# ProPrj_New_Project_2025-04-16_15-56-37_2.net
KiCad netlist of a schematic drawn in EasyEDA Pro
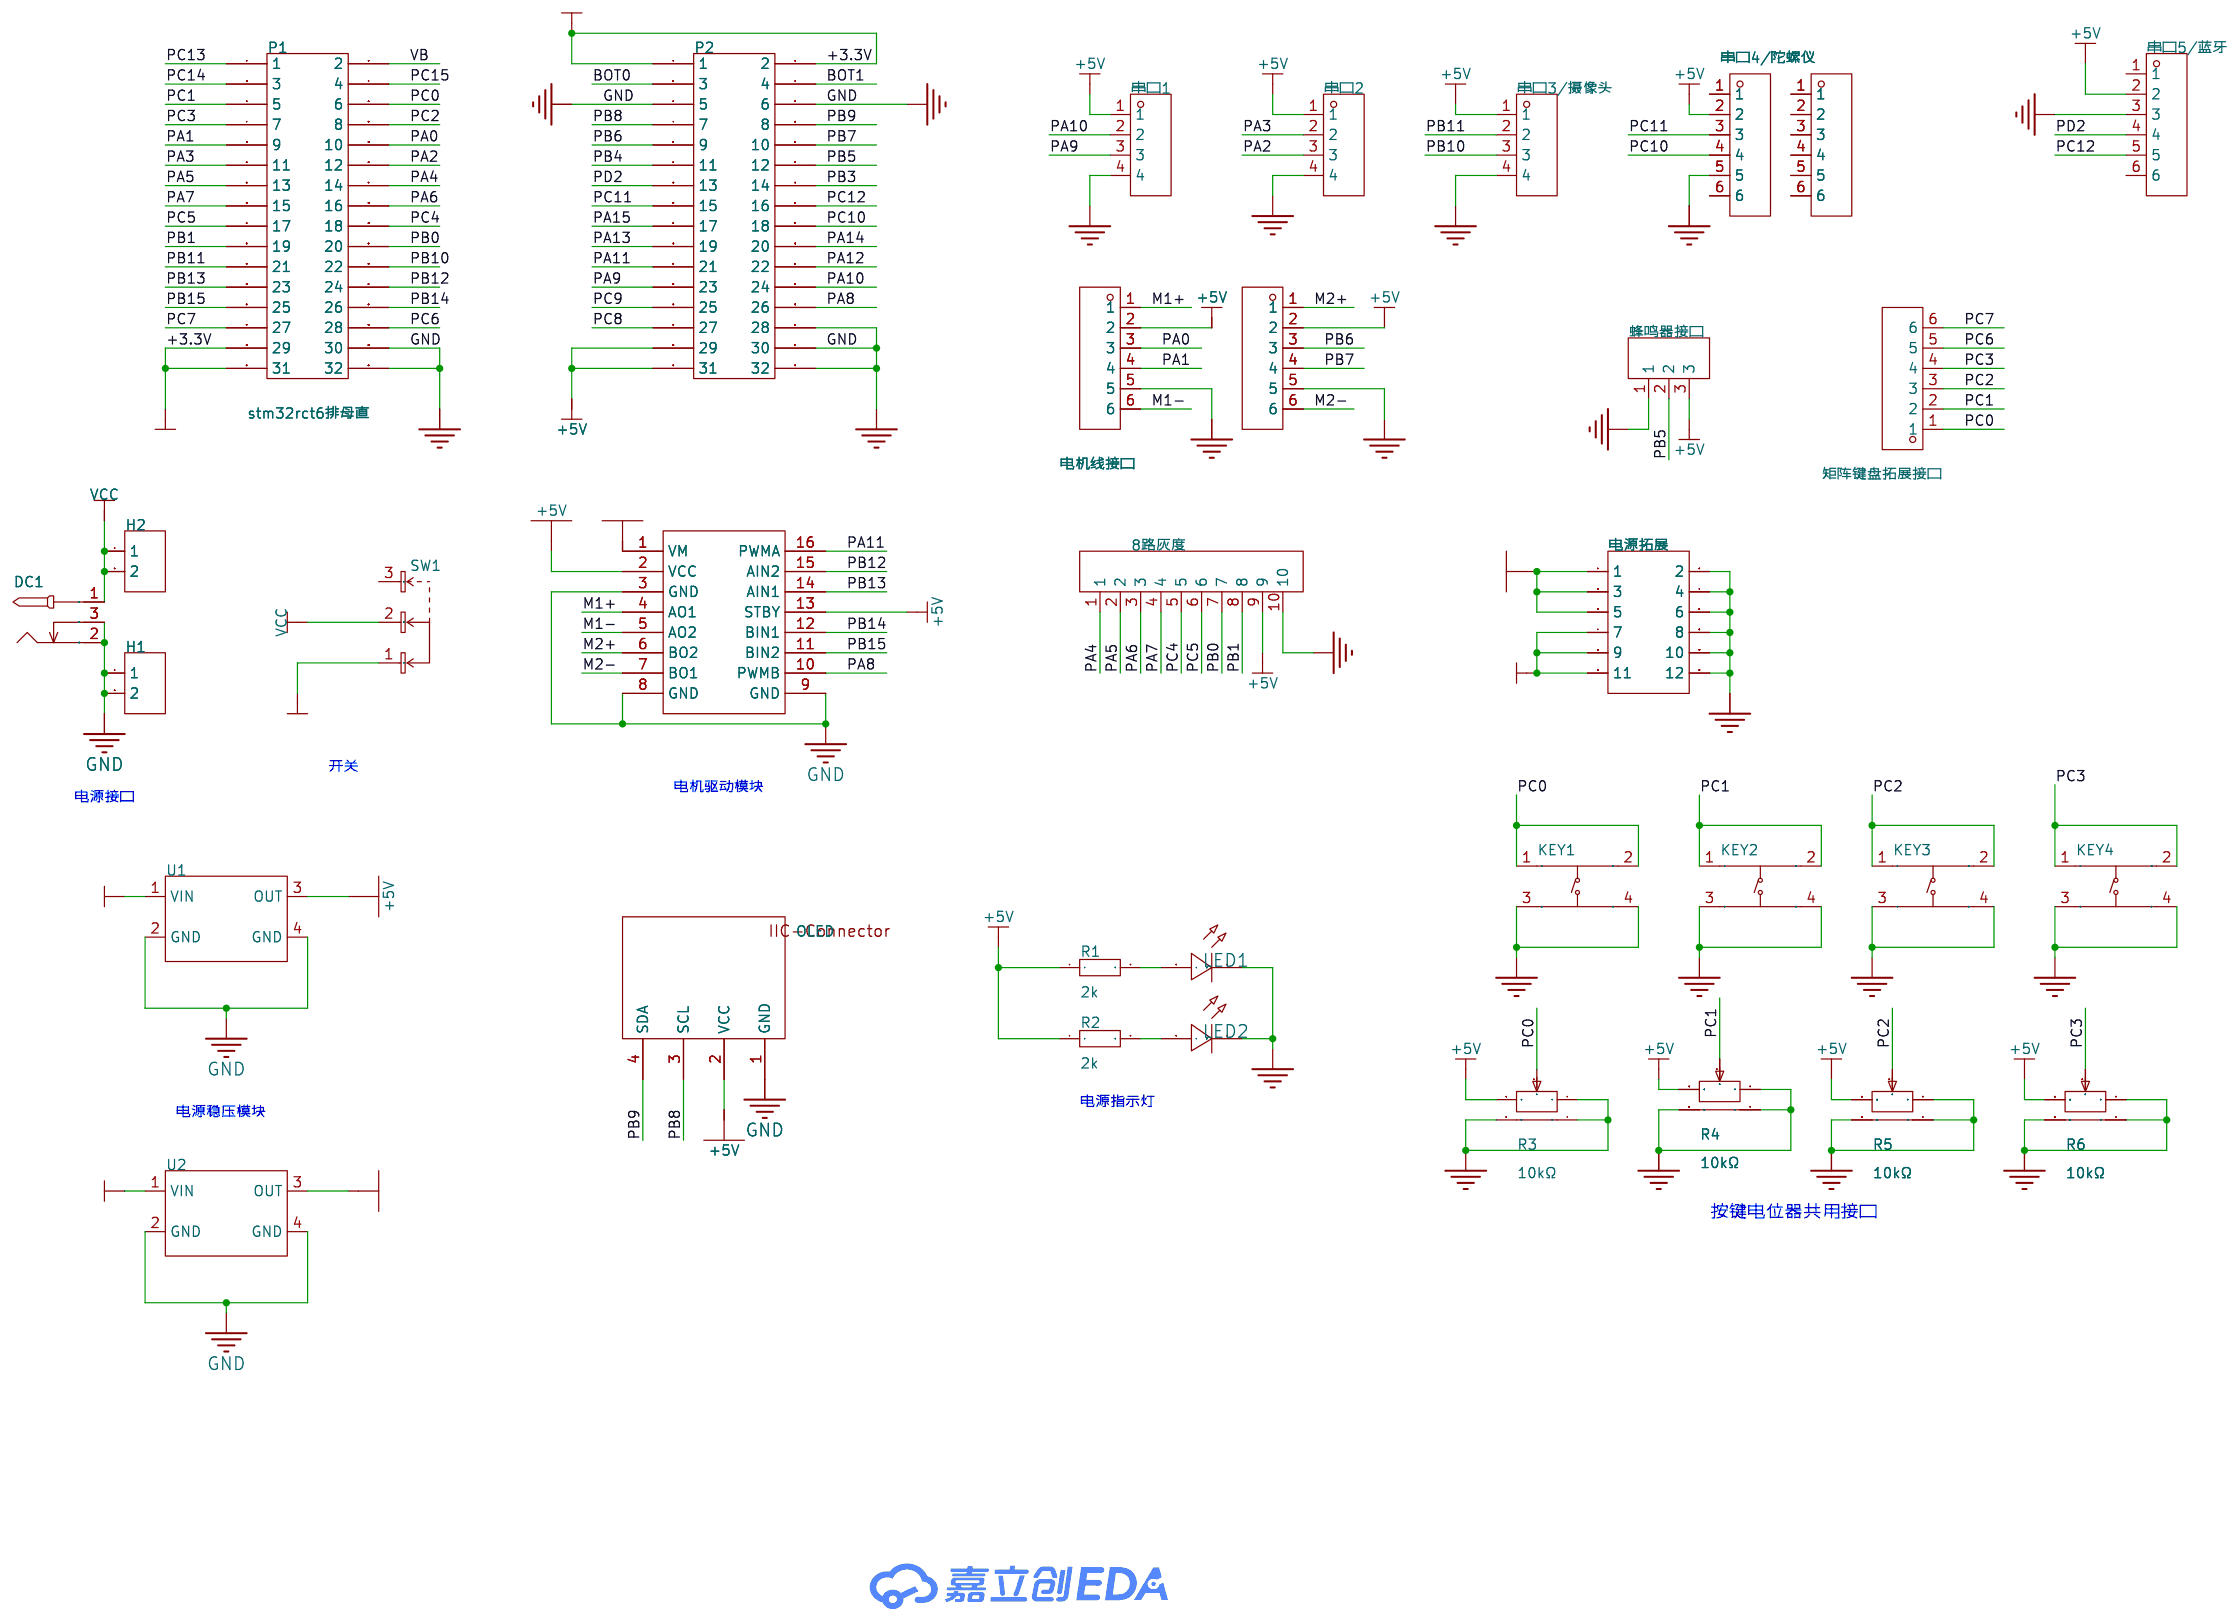
[diagram p0: schematic sheet]

(export (version "E")
  (design (tool "Eeschema 10.0.6"))
  (components
    (comp (ref "8路灰度")
      (value "~")
      (footprint "easyedapro:HDR-TH_10P-P2.54-V-F")
      (libsource (lib "easyedapro") (part "X5511FV-10-C70D30-1000"))
    )
    (comp (ref "DC1")
      (value "~")
      (footprint "easyedapro:DC-005_2.5")
      (libsource (lib "easyedapro") (part "DC-005_2.5"))
    )
    (comp (ref "H1")
      (value "~")
      (footprint "easyedapro:HDR-TH_2P-P2.54-V-F")
      (libsource (lib "easyedapro") (part "Header-Female-2.54_1x2"))
    )
    (comp (ref "H2")
      (value "~")
      (footprint "easyedapro:HDR-TH_2P-P2.54-V-F")
      (libsource (lib "easyedapro") (part "Header-Female-2.54_1x2"))
    )
    (comp (ref "H8")
      (value "~")
      (footprint "easyedapro:HDR-TH_6P-P2.54-V-F")
      (libsource (lib "easyedapro") (part "Header-Female-2.54_1x6"))
    )
    (comp (ref "KEY1")
      (value "TS665CJ")
      (footprint "easyedapro:SW-TH_4P-L6.0-W6.0-P4.50-LS6.5")
      (description "电路结构:单刀单掷;按钮形状:圆形按钮;安装方式:直插;开关长度:6mm;开关宽度:6mm;开关高度:5mm;触点电流:50mA;额定电压(DC):12V;带灯:-;机械寿命:-;")
      (fields (field (name "Manufacturer") "SHOU HAN(首韩)"))
      (libsource (lib "easyedapro") (part "TS665CJ"))
    )
    (comp (ref "KEY2")
      (value "TS665CJ")
      (footprint "easyedapro:SW-TH_4P-L6.0-W6.0-P4.50-LS6.5")
      (description "电路结构:单刀单掷;按钮形状:圆形按钮;安装方式:直插;开关长度:6mm;开关宽度:6mm;开关高度:5mm;触点电流:50mA;额定电压(DC):12V;带灯:-;机械寿命:-;")
      (fields (field (name "Manufacturer") "SHOU HAN(首韩)"))
      (libsource (lib "easyedapro") (part "TS665CJ"))
    )
    (comp (ref "KEY3")
      (value "TS665CJ")
      (footprint "easyedapro:SW-TH_4P-L6.0-W6.0-P4.50-LS6.5")
      (description "电路结构:单刀单掷;按钮形状:圆形按钮;安装方式:直插;开关长度:6mm;开关宽度:6mm;开关高度:5mm;触点电流:50mA;额定电压(DC):12V;带灯:-;机械寿命:-;")
      (fields (field (name "Manufacturer") "SHOU HAN(首韩)"))
      (libsource (lib "easyedapro") (part "TS665CJ"))
    )
    (comp (ref "KEY4")
      (value "TS665CJ")
      (footprint "easyedapro:SW-TH_4P-L6.0-W6.0-P4.50-LS6.5")
      (description "电路结构:单刀单掷;按钮形状:圆形按钮;安装方式:直插;开关长度:6mm;开关宽度:6mm;开关高度:5mm;触点电流:50mA;额定电压(DC):12V;带灯:-;机械寿命:-;")
      (fields (field (name "Manufacturer") "SHOU HAN(首韩)"))
      (libsource (lib "easyedapro") (part "TS665CJ"))
    )
    (comp (ref "LED1")
      (value "~")
      (footprint "easyedapro:LED_0603")
      (libsource (lib "easyedapro") (part "LED_R"))
    )
    (comp (ref "LED2")
      (value "~")
      (footprint "easyedapro:LED_0603")
      (libsource (lib "easyedapro") (part "LED_R"))
    )
    (comp (ref "OLED")
      (value "~")
      (fields (field (name "Manufacturer Part") "0.96OLED_4P_MODULE_JX"))
      (libsource (lib "easyedapro") (part "0.96OLED_4P_MODULE_JX"))
    )
    (comp (ref "P1")
      (value "stm32rct6排母直")
      (footprint "easyedapro:HDR-TH_32P-P2.54-V-F-R2-C16-S2.54")
      (description "圆针/方针:-;额定电流:-;额定电压:-;配合针长度:-;塑高:-;触头材质:-;")
      (libsource (lib "easyedapro") (part "2.54mm,2×16Double row female"))
    )
    (comp (ref "P2")
      (value "stm32rct6排母直")
      (footprint "easyedapro:HDR-TH_32P-P2.54-V-F-R2-C16-S2.54")
      (description "圆针/方针:-;额定电流:-;额定电压:-;配合针长度:-;塑高:-;触头材质:-;")
      (libsource (lib "easyedapro") (part "2.54mm,2×16Double row female"))
    )
    (comp (ref "R1") (value "2k") (footprint "easyedapro:R0603") (libsource (lib "easyedapro") (part "电阻")))
    (comp (ref "R2") (value "2k") (footprint "easyedapro:R0603") (libsource (lib "easyedapro") (part "电阻")))
    (comp (ref "R3")
      (value "10kΩ")
      (footprint "easyedapro:RES-ADJ-TH_RK09K1130AJ3")
      (description "阻值:10kΩ;精度:±20%;功率:50mW;")
      (fields
        (field (name "Manufacturer Part") "RK09K1130AP5")
        (field (name "Manufacturer") "ALPSALPINE(阿尔卑斯阿尔派)")
      )
      (libsource (lib "easyedapro") (part "RK09K1130AP5"))
    )
    (comp (ref "R4")
      (value "10kΩ")
      (footprint "easyedapro:RES-ADJ-TH_RK09K1130AJ3")
      (description "阻值:10kΩ;精度:±20%;功率:50mW;")
      (fields
        (field (name "Manufacturer Part") "RK09K1130AP5")
        (field (name "Manufacturer") "ALPSALPINE(阿尔卑斯阿尔派)")
      )
      (libsource (lib "easyedapro") (part "RK09K1130AP5"))
    )
    (comp (ref "R5")
      (value "10kΩ")
      (footprint "easyedapro:RES-ADJ-TH_RK09K1130AJ3")
      (description "阻值:10kΩ;精度:±20%;功率:50mW;")
      (fields
        (field (name "Manufacturer Part") "RK09K1130AP5")
        (field (name "Manufacturer") "ALPSALPINE(阿尔卑斯阿尔派)")
      )
      (libsource (lib "easyedapro") (part "RK09K1130AP5"))
    )
    (comp (ref "R6")
      (value "10kΩ")
      (footprint "easyedapro:RES-ADJ-TH_RK09K1130AJ3")
      (description "阻值:10kΩ;精度:±20%;功率:50mW;")
      (fields
        (field (name "Manufacturer Part") "RK09K1130AP5")
        (field (name "Manufacturer") "ALPSALPINE(阿尔卑斯阿尔派)")
      )
      (libsource (lib "easyedapro") (part "RK09K1130AP5"))
    )
    (comp (ref "SW1")
      (value "SS-12D06L5")
      (footprint "easyedapro:SW-TH_3P-P4.70_L11.1-W12.7")
      (description "电路结构:单刀双掷;安装方式:侧插;开关颜色:黑色;额定电流(DC):3A;额定电压(DC):250V;额定电流(AC):3A;额定电压(AC):250V;机械寿命:1万次;")
      (fields (field (name "Manufacturer") "XKB Connectivity(中国星坤)"))
      (libsource (lib "easyedapro") (part "SS-12D06L5"))
    )
    (comp (ref "U1")
      (value "~")
      (footprint "easyedapro:MP1584模块")
      (libsource (lib "easyedapro") (part "MP1584模块"))
    )
    (comp (ref "U2")
      (value "~")
      (footprint "easyedapro:MP1584模块")
      (libsource (lib "easyedapro") (part "MP1584模块"))
    )
    (comp (ref "U3")
      (value "PH2.0-6P")
      (fields (field (name "Manufacturer Part") "PH2.0-4P") (field (name "Manufacturer") "CAX(创都)"))
      (libsource (lib "easyedapro") (part "PH2.0-6P"))
    )
    (comp (ref "U5") (value "~") (libsource (lib "easyedapro") (part "TB6612FNG模块")))
    (comp (ref "串口1")
      (value "~")
      (footprint "easyedapro:HDR-TH_4P-P2.54-V-F")
      (libsource (lib "easyedapro") (part "2.54-1*4P母"))
    )
    (comp (ref "串口2")
      (value "~")
      (footprint "easyedapro:HDR-TH_4P-P2.54-V-F")
      (libsource (lib "easyedapro") (part "2.54-1*4P母"))
    )
    (comp (ref "串口3/摄像头")
      (value "~")
      (footprint "easyedapro:HDR-TH_4P-P2.54-V-F")
      (libsource (lib "easyedapro") (part "2.54-1*4P母"))
    )
    (comp (ref "串口4/陀螺仪")
      (value "~")
      (footprint "easyedapro:HDR-TH_6P-P2.54-V-F")
      (libsource (lib "easyedapro") (part "Header-Female-2.54_1x6"))
    )
    (comp (ref "串口5/蓝牙")
      (value "~")
      (footprint "easyedapro:HDR-TH_6P-P2.54-V-F")
      (libsource (lib "easyedapro") (part "Header-Female-2.54_1x6"))
    )
    (comp (ref "电机线接口")
      (value "PH2.0-6P")
      (fields (field (name "Manufacturer Part") "PH2.0-4P") (field (name "Manufacturer") "CAX(创都)"))
      (libsource (lib "easyedapro") (part "PH2.0-6P"))
    )
    (comp (ref "电源拓展")
      (value "~")
      (footprint "easyedapro:HDR-TH_12P-P2.54-V-M-R2-C6-S2.54")
      (libsource (lib "easyedapro") (part "HDR-F-2.54_2x6"))
    )
    (comp (ref "矩阵键盘拓展接口")
      (value "~")
      (footprint "easyedapro:HDR-TH_6P-P2.54-V-F")
      (libsource (lib "easyedapro") (part "Header-Female-2.54_1x6"))
    )
    (comp (ref "蜂鸣器接口")
      (value "~")
      (footprint "easyedapro:HDR-TH_3P-P2.54-V-F")
      (libsource (lib "easyedapro") (part "PM254V-11-03-H85"))
    )
  )
  (nets
    (net (code "1") (name "+3.3V") (class "Default")
      (node (ref "P1") (pin "29") (pinfunction "29_29") (pintype "input"))
      (node (ref "P1") (pin "31") (pinfunction "31_31") (pintype "input"))
      (node (ref "P2") (pin "1") (pinfunction "1_1") (pintype "input"))
      (node (ref "P2") (pin "2") (pinfunction "2_2") (pintype "input"))
      (node (ref "电源拓展") (pin "11") (pinfunction "11_11") (pintype "input"))
      (node (ref "电源拓展") (pin "7") (pinfunction "7_7") (pintype "input"))
      (node (ref "电源拓展") (pin "9") (pinfunction "9_9") (pintype "input"))
    )
    (net (code "2") (name "+5V") (class "Default")
      (node (ref "8路灰度") (pin "9") (pinfunction "9_9") (pintype "unspecified"))
      (node (ref "OLED") (pin "2") (pinfunction "VCC_2") (pintype "input"))
      (node (ref "P2") (pin "29") (pinfunction "29_29") (pintype "input"))
      (node (ref "P2") (pin "31") (pinfunction "31_31") (pintype "input"))
      (node (ref "R1") (pin "1") (pinfunction "1_1") (pintype "input"))
      (node (ref "R2") (pin "1") (pinfunction "1_1") (pintype "input"))
      (node (ref "R3") (pin "3") (pinfunction "3_3") (pintype "input"))
      (node (ref "R4") (pin "3") (pinfunction "3_3") (pintype "input"))
      (node (ref "R5") (pin "3") (pinfunction "3_3") (pintype "input"))
      (node (ref "R6") (pin "3") (pinfunction "3_3") (pintype "input"))
      (node (ref "U1") (pin "3") (pinfunction "OUT_3") (pintype "unspecified"))
      (node (ref "U3") (pin "2") (pinfunction "2_2") (pintype "input"))
      (node (ref "U5") (pin "13") (pinfunction "STBY_13") (pintype "input"))
      (node (ref "U5") (pin "2") (pinfunction "VCC_2") (pintype "input"))
      (node (ref "串口1") (pin "1") (pinfunction "1_1") (pintype "unspecified"))
      (node (ref "串口2") (pin "1") (pinfunction "1_1") (pintype "unspecified"))
      (node (ref "串口3/摄像头") (pin "1") (pinfunction "1_1") (pintype "unspecified"))
      (node (ref "串口4/陀螺仪") (pin "2") (pinfunction "2_2") (pintype "unspecified"))
      (node (ref "串口5/蓝牙") (pin "2") (pinfunction "2_2") (pintype "unspecified"))
      (node (ref "电机线接口") (pin "2") (pinfunction "2_2") (pintype "input"))
      (node (ref "蜂鸣器接口") (pin "3") (pinfunction "3_3") (pintype "unspecified"))
    )
    (net (code "3") (name "+12V") (class "Default")
      (node (ref "SW1") (pin "1") (pinfunction "1_1") (pintype "unspecified"))
      (node (ref "U1") (pin "1") (pinfunction "VIN_1") (pintype "unspecified"))
      (node (ref "U2") (pin "1") (pinfunction "VIN_1") (pintype "unspecified"))
      (node (ref "U5") (pin "1") (pinfunction "VM_1") (pintype "input"))
    )
    (net (code "4") (name "/BOT0") (class "Default")
      (node (ref "P2") (pin "3") (pinfunction "3_3") (pintype "input"))
    )
    (net (code "5") (name "/BOT1") (class "Default")
      (node (ref "P2") (pin "4") (pinfunction "4_4") (pintype "input"))
    )
    (net (code "6") (name "/M1+") (class "Default")
      (node (ref "U3") (pin "1") (pinfunction "1_1") (pintype "input"))
      (node (ref "U5") (pin "4") (pinfunction "AO1_4") (pintype "input"))
    )
    (net (code "7") (name "/M1-") (class "Default")
      (node (ref "U3") (pin "6") (pinfunction "6_6") (pintype "input"))
      (node (ref "U5") (pin "5") (pinfunction "AO2_5") (pintype "input"))
    )
    (net (code "8") (name "/M2+") (class "Default")
      (node (ref "U5") (pin "6") (pinfunction "BO2_6") (pintype "input"))
      (node (ref "电机线接口") (pin "1") (pinfunction "1_1") (pintype "input"))
    )
    (net (code "9") (name "/M2-") (class "Default")
      (node (ref "U5") (pin "7") (pinfunction "BO1_7") (pintype "input"))
      (node (ref "电机线接口") (pin "6") (pinfunction "6_6") (pintype "input"))
    )
    (net (code "10") (name "/PA0") (class "Default")
      (node (ref "P1") (pin "10") (pinfunction "10_10") (pintype "input"))
      (node (ref "U3") (pin "3") (pinfunction "3_3") (pintype "input"))
    )
    (net (code "11") (name "/PA1") (class "Default")
      (node (ref "P1") (pin "9") (pinfunction "9_9") (pintype "input"))
      (node (ref "U3") (pin "4") (pinfunction "4_4") (pintype "input"))
    )
    (net (code "12") (name "/PA2") (class "Default")
      (node (ref "P1") (pin "12") (pinfunction "12_12") (pintype "input"))
      (node (ref "串口2") (pin "3") (pinfunction "3_3") (pintype "unspecified"))
    )
    (net (code "13") (name "/PA3") (class "Default")
      (node (ref "P1") (pin "11") (pinfunction "11_11") (pintype "input"))
      (node (ref "串口2") (pin "2") (pinfunction "2_2") (pintype "unspecified"))
    )
    (net (code "14") (name "/PA4") (class "Default")
      (node (ref "8路灰度") (pin "1") (pinfunction "1_1") (pintype "unspecified"))
      (node (ref "P1") (pin "14") (pinfunction "14_14") (pintype "input"))
    )
    (net (code "15") (name "/PA5") (class "Default")
      (node (ref "8路灰度") (pin "2") (pinfunction "2_2") (pintype "unspecified"))
      (node (ref "P1") (pin "13") (pinfunction "13_13") (pintype "input"))
    )
    (net (code "16") (name "/PA6") (class "Default")
      (node (ref "8路灰度") (pin "3") (pinfunction "3_3") (pintype "unspecified"))
      (node (ref "P1") (pin "16") (pinfunction "16_16") (pintype "input"))
    )
    (net (code "17") (name "/PA7") (class "Default")
      (node (ref "8路灰度") (pin "4") (pinfunction "4_4") (pintype "unspecified"))
      (node (ref "P1") (pin "15") (pinfunction "15_15") (pintype "input"))
    )
    (net (code "18") (name "/PA8") (class "Default")
      (node (ref "P2") (pin "26") (pinfunction "26_26") (pintype "input"))
      (node (ref "U5") (pin "10") (pinfunction "PWMB_10") (pintype "input"))
    )
    (net (code "19") (name "/PA9") (class "Default")
      (node (ref "P2") (pin "23") (pinfunction "23_23") (pintype "input"))
      (node (ref "串口1") (pin "3") (pinfunction "3_3") (pintype "unspecified"))
    )
    (net (code "20") (name "/PA10") (class "Default")
      (node (ref "P2") (pin "24") (pinfunction "24_24") (pintype "input"))
      (node (ref "串口1") (pin "2") (pinfunction "2_2") (pintype "unspecified"))
    )
    (net (code "21") (name "/PA11") (class "Default")
      (node (ref "P2") (pin "21") (pinfunction "21_21") (pintype "input"))
      (node (ref "U5") (pin "16") (pinfunction "PWMA_16") (pintype "input"))
    )
    (net (code "22") (name "/PA12") (class "Default")
      (node (ref "P2") (pin "22") (pinfunction "22_22") (pintype "input"))
    )
    (net (code "23") (name "/PA13") (class "Default")
      (node (ref "P2") (pin "19") (pinfunction "19_19") (pintype "input"))
    )
    (net (code "24") (name "/PA14") (class "Default")
      (node (ref "P2") (pin "20") (pinfunction "20_20") (pintype "input"))
    )
    (net (code "25") (name "/PA15") (class "Default")
      (node (ref "P2") (pin "17") (pinfunction "17_17") (pintype "input"))
    )
    (net (code "26") (name "/PB0") (class "Default")
      (node (ref "8路灰度") (pin "7") (pinfunction "7_7") (pintype "unspecified"))
      (node (ref "P1") (pin "20") (pinfunction "20_20") (pintype "input"))
    )
    (net (code "27") (name "/PB1") (class "Default")
      (node (ref "8路灰度") (pin "8") (pinfunction "8_8") (pintype "unspecified"))
      (node (ref "P1") (pin "19") (pinfunction "19_19") (pintype "input"))
    )
    (net (code "28") (name "/PB3") (class "Default")
      (node (ref "P2") (pin "14") (pinfunction "14_14") (pintype "input"))
    )
    (net (code "29") (name "/PB4") (class "Default")
      (node (ref "P2") (pin "11") (pinfunction "11_11") (pintype "input"))
    )
    (net (code "30") (name "/PB5") (class "Default")
      (node (ref "P2") (pin "12") (pinfunction "12_12") (pintype "input"))
      (node (ref "蜂鸣器接口") (pin "2") (pinfunction "2_2") (pintype "unspecified"))
    )
    (net (code "31") (name "/PB6") (class "Default")
      (node (ref "P2") (pin "9") (pinfunction "9_9") (pintype "input"))
      (node (ref "电机线接口") (pin "3") (pinfunction "3_3") (pintype "input"))
    )
    (net (code "32") (name "/PB7") (class "Default")
      (node (ref "P2") (pin "10") (pinfunction "10_10") (pintype "input"))
      (node (ref "电机线接口") (pin "4") (pinfunction "4_4") (pintype "input"))
    )
    (net (code "33") (name "/PB8") (class "Default")
      (node (ref "OLED") (pin "3") (pinfunction "SCL_3") (pintype "input"))
      (node (ref "P2") (pin "7") (pinfunction "7_7") (pintype "input"))
    )
    (net (code "34") (name "/PB9") (class "Default")
      (node (ref "OLED") (pin "4") (pinfunction "SDA_4") (pintype "input"))
      (node (ref "P2") (pin "8") (pinfunction "8_8") (pintype "input"))
    )
    (net (code "35") (name "/PB10") (class "Default")
      (node (ref "P1") (pin "22") (pinfunction "22_22") (pintype "input"))
      (node (ref "串口3/摄像头") (pin "3") (pinfunction "3_3") (pintype "unspecified"))
    )
    (net (code "36") (name "/PB11") (class "Default")
      (node (ref "P1") (pin "21") (pinfunction "21_21") (pintype "input"))
      (node (ref "串口3/摄像头") (pin "2") (pinfunction "2_2") (pintype "unspecified"))
    )
    (net (code "37") (name "/PB12") (class "Default")
      (node (ref "P1") (pin "24") (pinfunction "24_24") (pintype "input"))
      (node (ref "U5") (pin "15") (pinfunction "AIN2_15") (pintype "input"))
    )
    (net (code "38") (name "/PB13") (class "Default")
      (node (ref "P1") (pin "23") (pinfunction "23_23") (pintype "input"))
      (node (ref "U5") (pin "14") (pinfunction "AIN1_14") (pintype "input"))
    )
    (net (code "39") (name "/PB14") (class "Default")
      (node (ref "P1") (pin "26") (pinfunction "26_26") (pintype "input"))
      (node (ref "U5") (pin "12") (pinfunction "BIN1_12") (pintype "input"))
    )
    (net (code "40") (name "/PB15") (class "Default")
      (node (ref "P1") (pin "25") (pinfunction "25_25") (pintype "input"))
      (node (ref "U5") (pin "11") (pinfunction "BIN2_11") (pintype "input"))
    )
    (net (code "41") (name "/PC0") (class "Default")
      (node (ref "KEY1") (pin "1") (pinfunction "A_1") (pintype "unspecified"))
      (node (ref "KEY1") (pin "2") (pinfunction "B_2") (pintype "unspecified"))
      (node (ref "P1") (pin "6") (pinfunction "6_6") (pintype "input"))
      (node (ref "R3") (pin "2") (pinfunction "2_2") (pintype "input"))
      (node (ref "矩阵键盘拓展接口") (pin "1") (pinfunction "1_1") (pintype "unspecified"))
    )
    (net (code "42") (name "/PC1") (class "Default")
      (node (ref "KEY2") (pin "1") (pinfunction "A_1") (pintype "unspecified"))
      (node (ref "KEY2") (pin "2") (pinfunction "B_2") (pintype "unspecified"))
      (node (ref "P1") (pin "5") (pinfunction "5_5") (pintype "input"))
      (node (ref "R4") (pin "2") (pinfunction "2_2") (pintype "input"))
      (node (ref "矩阵键盘拓展接口") (pin "2") (pinfunction "2_2") (pintype "unspecified"))
    )
    (net (code "43") (name "/PC2") (class "Default")
      (node (ref "KEY3") (pin "1") (pinfunction "A_1") (pintype "unspecified"))
      (node (ref "KEY3") (pin "2") (pinfunction "B_2") (pintype "unspecified"))
      (node (ref "P1") (pin "8") (pinfunction "8_8") (pintype "input"))
      (node (ref "R5") (pin "2") (pinfunction "2_2") (pintype "input"))
      (node (ref "矩阵键盘拓展接口") (pin "3") (pinfunction "3_3") (pintype "unspecified"))
    )
    (net (code "44") (name "/PC3") (class "Default")
      (node (ref "KEY4") (pin "1") (pinfunction "A_1") (pintype "unspecified"))
      (node (ref "KEY4") (pin "2") (pinfunction "B_2") (pintype "unspecified"))
      (node (ref "P1") (pin "7") (pinfunction "7_7") (pintype "input"))
      (node (ref "R6") (pin "2") (pinfunction "2_2") (pintype "input"))
      (node (ref "矩阵键盘拓展接口") (pin "4") (pinfunction "4_4") (pintype "unspecified"))
    )
    (net (code "45") (name "/PC4") (class "Default")
      (node (ref "8路灰度") (pin "5") (pinfunction "5_5") (pintype "unspecified"))
      (node (ref "P1") (pin "18") (pinfunction "18_18") (pintype "input"))
    )
    (net (code "46") (name "/PC5") (class "Default")
      (node (ref "8路灰度") (pin "6") (pinfunction "6_6") (pintype "unspecified"))
      (node (ref "P1") (pin "17") (pinfunction "17_17") (pintype "input"))
    )
    (net (code "47") (name "/PC6") (class "Default")
      (node (ref "P1") (pin "28") (pinfunction "28_28") (pintype "input"))
      (node (ref "矩阵键盘拓展接口") (pin "5") (pinfunction "5_5") (pintype "unspecified"))
    )
    (net (code "48") (name "/PC7") (class "Default")
      (node (ref "P1") (pin "27") (pinfunction "27_27") (pintype "input"))
      (node (ref "矩阵键盘拓展接口") (pin "6") (pinfunction "6_6") (pintype "unspecified"))
    )
    (net (code "49") (name "/PC8") (class "Default")
      (node (ref "P2") (pin "27") (pinfunction "27_27") (pintype "input"))
    )
    (net (code "50") (name "/PC9") (class "Default")
      (node (ref "P2") (pin "25") (pinfunction "25_25") (pintype "input"))
    )
    (net (code "51") (name "/PC10") (class "Default")
      (node (ref "P2") (pin "18") (pinfunction "18_18") (pintype "input"))
      (node (ref "串口4/陀螺仪") (pin "4") (pinfunction "4_4") (pintype "unspecified"))
    )
    (net (code "52") (name "/PC11") (class "Default")
      (node (ref "P2") (pin "15") (pinfunction "15_15") (pintype "input"))
      (node (ref "串口4/陀螺仪") (pin "3") (pinfunction "3_3") (pintype "unspecified"))
    )
    (net (code "53") (name "/PC12") (class "Default")
      (node (ref "P2") (pin "16") (pinfunction "16_16") (pintype "input"))
      (node (ref "串口5/蓝牙") (pin "5") (pinfunction "5_5") (pintype "unspecified"))
    )
    (net (code "54") (name "/PC13") (class "Default")
      (node (ref "P1") (pin "1") (pinfunction "1_1") (pintype "input"))
    )
    (net (code "55") (name "/PC14") (class "Default")
      (node (ref "P1") (pin "3") (pinfunction "3_3") (pintype "input"))
    )
    (net (code "56") (name "/PC15") (class "Default")
      (node (ref "P1") (pin "4") (pinfunction "4_4") (pintype "input"))
    )
    (net (code "57") (name "/PD2") (class "Default")
      (node (ref "P2") (pin "13") (pinfunction "13_13") (pintype "input"))
      (node (ref "串口5/蓝牙") (pin "4") (pinfunction "4_4") (pintype "unspecified"))
    )
    (net (code "58") (name "/VB") (class "Default")
      (node (ref "P1") (pin "2") (pinfunction "2_2") (pintype "input"))
    )
    (net (code "59") (name "5V") (class "Default")
      (node (ref "U2") (pin "3") (pinfunction "OUT_3") (pintype "unspecified"))
      (node (ref "电源拓展") (pin "1") (pinfunction "1_1") (pintype "input"))
      (node (ref "电源拓展") (pin "3") (pinfunction "3_3") (pintype "input"))
      (node (ref "电源拓展") (pin "5") (pinfunction "5_5") (pintype "input"))
    )
    (net (code "60") (name "GND") (class "Default")
      (node (ref "8路灰度") (pin "10") (pinfunction "10_10") (pintype "unspecified"))
      (node (ref "DC1") (pin "2") (pinfunction "2_2") (pintype "input"))
      (node (ref "DC1") (pin "3") (pinfunction "3_3") (pintype "input"))
      (node (ref "H1") (pin "1") (pinfunction "1_1") (pintype "input"))
      (node (ref "H1") (pin "2") (pinfunction "2_2") (pintype "input"))
      (node (ref "KEY1") (pin "3") (pinfunction "C_3") (pintype "unspecified"))
      (node (ref "KEY1") (pin "4") (pinfunction "D_4") (pintype "unspecified"))
      (node (ref "KEY2") (pin "3") (pinfunction "C_3") (pintype "unspecified"))
      (node (ref "KEY2") (pin "4") (pinfunction "D_4") (pintype "unspecified"))
      (node (ref "KEY3") (pin "3") (pinfunction "C_3") (pintype "unspecified"))
      (node (ref "KEY3") (pin "4") (pinfunction "D_4") (pintype "unspecified"))
      (node (ref "KEY4") (pin "3") (pinfunction "C_3") (pintype "unspecified"))
      (node (ref "KEY4") (pin "4") (pinfunction "D_4") (pintype "unspecified"))
      (node (ref "LED1") (pin "1") (pinfunction "C_1") (pintype "input"))
      (node (ref "LED2") (pin "1") (pinfunction "C_1") (pintype "input"))
      (node (ref "OLED") (pin "1") (pinfunction "GND_1") (pintype "input"))
      (node (ref "P1") (pin "30") (pinfunction "30_30") (pintype "input"))
      (node (ref "P1") (pin "32") (pinfunction "32_32") (pintype "input"))
      (node (ref "P2") (pin "28") (pinfunction "28_28") (pintype "input"))
      (node (ref "P2") (pin "30") (pinfunction "30_30") (pintype "input"))
      (node (ref "P2") (pin "32") (pinfunction "32_32") (pintype "input"))
      (node (ref "P2") (pin "5") (pinfunction "5_5") (pintype "input"))
      (node (ref "P2") (pin "6") (pinfunction "6_6") (pintype "input"))
      (node (ref "R3") (pin "1") (pinfunction "1_1") (pintype "input"))
      (node (ref "R3") (pin "4") (pinfunction "4_4") (pintype "input"))
      (node (ref "R3") (pin "5") (pinfunction "5_5") (pintype "input"))
      (node (ref "R4") (pin "1") (pinfunction "1_1") (pintype "input"))
      (node (ref "R4") (pin "4") (pinfunction "4_4") (pintype "input"))
      (node (ref "R4") (pin "5") (pinfunction "5_5") (pintype "input"))
      (node (ref "R5") (pin "1") (pinfunction "1_1") (pintype "input"))
      (node (ref "R5") (pin "4") (pinfunction "4_4") (pintype "input"))
      (node (ref "R5") (pin "5") (pinfunction "5_5") (pintype "input"))
      (node (ref "R6") (pin "1") (pinfunction "1_1") (pintype "input"))
      (node (ref "R6") (pin "4") (pinfunction "4_4") (pintype "input"))
      (node (ref "R6") (pin "5") (pinfunction "5_5") (pintype "input"))
      (node (ref "U1") (pin "2") (pinfunction "GND_2") (pintype "unspecified"))
      (node (ref "U1") (pin "4") (pinfunction "GND_4") (pintype "unspecified"))
      (node (ref "U2") (pin "2") (pinfunction "GND_2") (pintype "unspecified"))
      (node (ref "U2") (pin "4") (pinfunction "GND_4") (pintype "unspecified"))
      (node (ref "U3") (pin "5") (pinfunction "5_5") (pintype "input"))
      (node (ref "U5") (pin "3") (pinfunction "GND_3") (pintype "input"))
      (node (ref "U5") (pin "8") (pinfunction "GND_8") (pintype "input"))
      (node (ref "U5") (pin "9") (pinfunction "GND_9") (pintype "input"))
      (node (ref "串口1") (pin "4") (pinfunction "4_4") (pintype "unspecified"))
      (node (ref "串口2") (pin "4") (pinfunction "4_4") (pintype "unspecified"))
      (node (ref "串口3/摄像头") (pin "4") (pinfunction "4_4") (pintype "unspecified"))
      (node (ref "串口4/陀螺仪") (pin "5") (pinfunction "5_5") (pintype "unspecified"))
      (node (ref "串口5/蓝牙") (pin "3") (pinfunction "3_3") (pintype "unspecified"))
      (node (ref "电机线接口") (pin "5") (pinfunction "5_5") (pintype "input"))
      (node (ref "电源拓展") (pin "10") (pinfunction "10_10") (pintype "input"))
      (node (ref "电源拓展") (pin "12") (pinfunction "12_12") (pintype "input"))
      (node (ref "电源拓展") (pin "2") (pinfunction "2_2") (pintype "input"))
      (node (ref "电源拓展") (pin "4") (pinfunction "4_4") (pintype "input"))
      (node (ref "电源拓展") (pin "6") (pinfunction "6_6") (pintype "input"))
      (node (ref "电源拓展") (pin "8") (pinfunction "8_8") (pintype "input"))
      (node (ref "蜂鸣器接口") (pin "1") (pinfunction "1_1") (pintype "unspecified"))
    )
    (net (code "61") (name "Net-(LED1-A)") (class "Default")
      (node (ref "LED1") (pin "2") (pinfunction "A_2") (pintype "input"))
      (node (ref "R1") (pin "2") (pinfunction "2_2") (pintype "input"))
    )
    (net (code "62") (name "Net-(LED2-A)") (class "Default")
      (node (ref "LED2") (pin "2") (pinfunction "A_2") (pintype "input"))
      (node (ref "R2") (pin "2") (pinfunction "2_2") (pintype "input"))
    )
    (net (code "63") (name "VCC") (class "Default")
      (node (ref "DC1") (pin "1") (pinfunction "4_1") (pintype "input"))
      (node (ref "H2") (pin "1") (pinfunction "1_1") (pintype "input"))
      (node (ref "H2") (pin "2") (pinfunction "2_2") (pintype "input"))
      (node (ref "SW1") (pin "2") (pinfunction "2_2") (pintype "unspecified"))
    )
    (net (code "64") (name "unconnected-(H8-Pad1)") (class "Default")
      (node (ref "H8") (pin "1") (pinfunction "1_1") (pintype "unspecified"))
    )
    (net (code "65") (name "unconnected-(H8-Pad2)") (class "Default")
      (node (ref "H8") (pin "2") (pinfunction "2_2") (pintype "unspecified"))
    )
    (net (code "66") (name "unconnected-(H8-Pad3)") (class "Default")
      (node (ref "H8") (pin "3") (pinfunction "3_3") (pintype "unspecified"))
    )
    (net (code "67") (name "unconnected-(H8-Pad4)") (class "Default")
      (node (ref "H8") (pin "4") (pinfunction "4_4") (pintype "unspecified"))
    )
    (net (code "68") (name "unconnected-(H8-Pad5)") (class "Default")
      (node (ref "H8") (pin "5") (pinfunction "5_5") (pintype "unspecified"))
    )
    (net (code "69") (name "unconnected-(H8-Pad6)") (class "Default")
      (node (ref "H8") (pin "6") (pinfunction "6_6") (pintype "unspecified"))
    )
    (net (code "70") (name "unconnected-(SW1-Pad3)") (class "Default")
      (node (ref "SW1") (pin "3") (pinfunction "3_3") (pintype "unspecified"))
    )
    (net (code "71") (name "unconnected-(串口4/陀螺仪-Pad1)") (class "Default")
      (node (ref "串口4/陀螺仪") (pin "1") (pinfunction "1_1") (pintype "unspecified"))
    )
    (net (code "72") (name "unconnected-(串口4/陀螺仪-Pad6)") (class "Default")
      (node (ref "串口4/陀螺仪") (pin "6") (pinfunction "6_6") (pintype "unspecified"))
    )
    (net (code "73") (name "unconnected-(串口5/蓝牙-Pad1)") (class "Default")
      (node (ref "串口5/蓝牙") (pin "1") (pinfunction "1_1") (pintype "unspecified"))
    )
    (net (code "74") (name "unconnected-(串口5/蓝牙-Pad6)") (class "Default")
      (node (ref "串口5/蓝牙") (pin "6") (pinfunction "6_6") (pintype "unspecified"))
    )
  )
)
